# nav.net
KiCad netlist of a schematic drawn in EAGLE
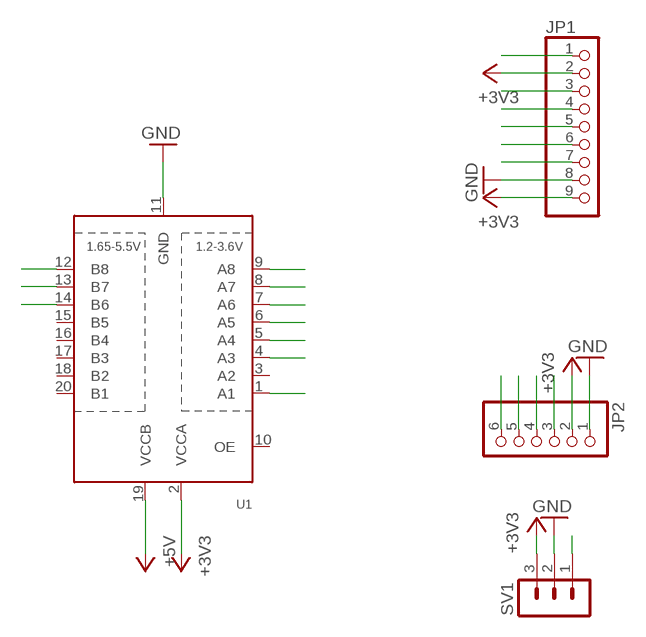
[diagram p0: schematic, sheet 1]

(export (version "E")
  (design (tool "Eeschema 10.0.6"))
  (components
    (comp (ref "JP1")
      (value "PINHD-1X9")
      (footprint "eagle-import:1X09-BIG")
      (libsource (lib "eagle-import") (part "PINHD-1X9"))
    )
    (comp (ref "JP2")
      (value "PINHD-1X6")
      (footprint "eagle-import:1X06")
      (libsource (lib "eagle-import") (part "PINHD-1X6"))
    )
    (comp (ref "SV1")
      (value "MA03-1")
      (footprint "eagle-import:MA03-1")
      (libsource (lib "eagle-import") (part "MA03-1"))
    )
    (comp (ref "U1")
      (value "TXB0108PWR")
      (footprint "eagle-import:TSSOP20")
      (libsource (lib "eagle-import") (part "TXB0108PWR"))
    )
  )
  (nets
    (net (code "1") (name "+3V3") (class "Default")
      (node (ref "JP1") (pin "2") (pinfunction "2_2") (pintype "passive"))
      (node (ref "JP1") (pin "9") (pinfunction "9_9") (pintype "passive"))
      (node (ref "JP2") (pin "2") (pinfunction "2_2") (pintype "passive"))
      (node (ref "SV1") (pin "3") (pinfunction "3_3") (pintype "passive"))
      (node (ref "U1") (pin "2") (pinfunction "VCCA_2") (pintype "bidirectional"))
    )
    (net (code "2") (name "+5V") (class "Default")
      (node (ref "U1") (pin "19") (pinfunction "VCCB_19") (pintype "bidirectional"))
    )
    (net (code "3") (name "/MISO3") (class "Default")
      (node (ref "JP1") (pin "1") (pinfunction "1_1") (pintype "passive"))
      (node (ref "JP2") (pin "3") (pinfunction "3_3") (pintype "passive"))
      (node (ref "U1") (pin "9") (pinfunction "A8_9") (pintype "bidirectional"))
    )
    (net (code "4") (name "/MOSI3") (class "Default")
      (node (ref "JP1") (pin "4") (pinfunction "4_4") (pintype "passive"))
      (node (ref "JP2") (pin "4") (pinfunction "4_4") (pintype "passive"))
      (node (ref "U1") (pin "8") (pinfunction "A7_8") (pintype "bidirectional"))
    )
    (net (code "5") (name "/SCK3") (class "Default")
      (node (ref "JP1") (pin "3") (pinfunction "3_3") (pintype "passive"))
      (node (ref "JP2") (pin "5") (pinfunction "5_5") (pintype "passive"))
      (node (ref "U1") (pin "7") (pinfunction "A6_7") (pintype "bidirectional"))
    )
    (net (code "6") (name "/SCREEN_CS") (class "Default")
      (node (ref "JP1") (pin "7") (pinfunction "7_7") (pintype "passive"))
      (node (ref "U1") (pin "4") (pinfunction "A3_4") (pintype "bidirectional"))
    )
    (net (code "7") (name "/SCREEN_DC") (class "Default")
      (node (ref "JP1") (pin "5") (pinfunction "5_5") (pintype "passive"))
      (node (ref "U1") (pin "6") (pinfunction "A5_6") (pintype "bidirectional"))
    )
    (net (code "8") (name "/SCREEN_RESET") (class "Default")
      (node (ref "JP1") (pin "6") (pinfunction "6_6") (pintype "passive"))
      (node (ref "U1") (pin "5") (pinfunction "A4_5") (pintype "bidirectional"))
    )
    (net (code "9") (name "/SD_CS") (class "Default")
      (node (ref "JP2") (pin "6") (pinfunction "6_6") (pintype "passive"))
      (node (ref "U1") (pin "1") (pinfunction "A1_1") (pintype "bidirectional"))
    )
    (net (code "10") (name "GND") (class "Default")
      (node (ref "JP1") (pin "8") (pinfunction "8_8") (pintype "passive"))
      (node (ref "JP2") (pin "1") (pinfunction "1_1") (pintype "passive"))
      (node (ref "SV1") (pin "2") (pinfunction "2_2") (pintype "passive"))
      (node (ref "U1") (pin "11") (pinfunction "GND_11") (pintype "bidirectional"))
    )
    (net (code "11") (name "unconnected-(SV1-Pad1)") (class "Default")
      (node (ref "SV1") (pin "1") (pinfunction "1_1") (pintype "passive"))
    )
    (net (code "12") (name "unconnected-(U1-A2-Pad3)") (class "Default")
      (node (ref "U1") (pin "3") (pinfunction "A2_3") (pintype "bidirectional"))
    )
    (net (code "13") (name "unconnected-(U1-B1-Pad20)") (class "Default")
      (node (ref "U1") (pin "20") (pinfunction "B1_20") (pintype "bidirectional"))
    )
    (net (code "14") (name "unconnected-(U1-B2-Pad18)") (class "Default")
      (node (ref "U1") (pin "18") (pinfunction "B2_18") (pintype "bidirectional"))
    )
    (net (code "15") (name "unconnected-(U1-B3-Pad17)") (class "Default")
      (node (ref "U1") (pin "17") (pinfunction "B3_17") (pintype "bidirectional"))
    )
    (net (code "16") (name "unconnected-(U1-B4-Pad16)") (class "Default")
      (node (ref "U1") (pin "16") (pinfunction "B4_16") (pintype "bidirectional"))
    )
    (net (code "17") (name "unconnected-(U1-B5-Pad15)") (class "Default")
      (node (ref "U1") (pin "15") (pinfunction "B5_15") (pintype "bidirectional"))
    )
    (net (code "18") (name "unconnected-(U1-B6-Pad14)") (class "Default")
      (node (ref "U1") (pin "14") (pinfunction "B6_14") (pintype "bidirectional"))
    )
    (net (code "19") (name "unconnected-(U1-B7-Pad13)") (class "Default")
      (node (ref "U1") (pin "13") (pinfunction "B7_13") (pintype "bidirectional"))
    )
    (net (code "20") (name "unconnected-(U1-B8-Pad12)") (class "Default")
      (node (ref "U1") (pin "12") (pinfunction "B8_12") (pintype "bidirectional"))
    )
    (net (code "21") (name "unconnected-(U1-OE-Pad10)") (class "Default")
      (node (ref "U1") (pin "10") (pinfunction "OE_10") (pintype "bidirectional"))
    )
  )
)
